# h2oiq_rev2.net
KiCad netlist of a schematic drawn in EAGLE
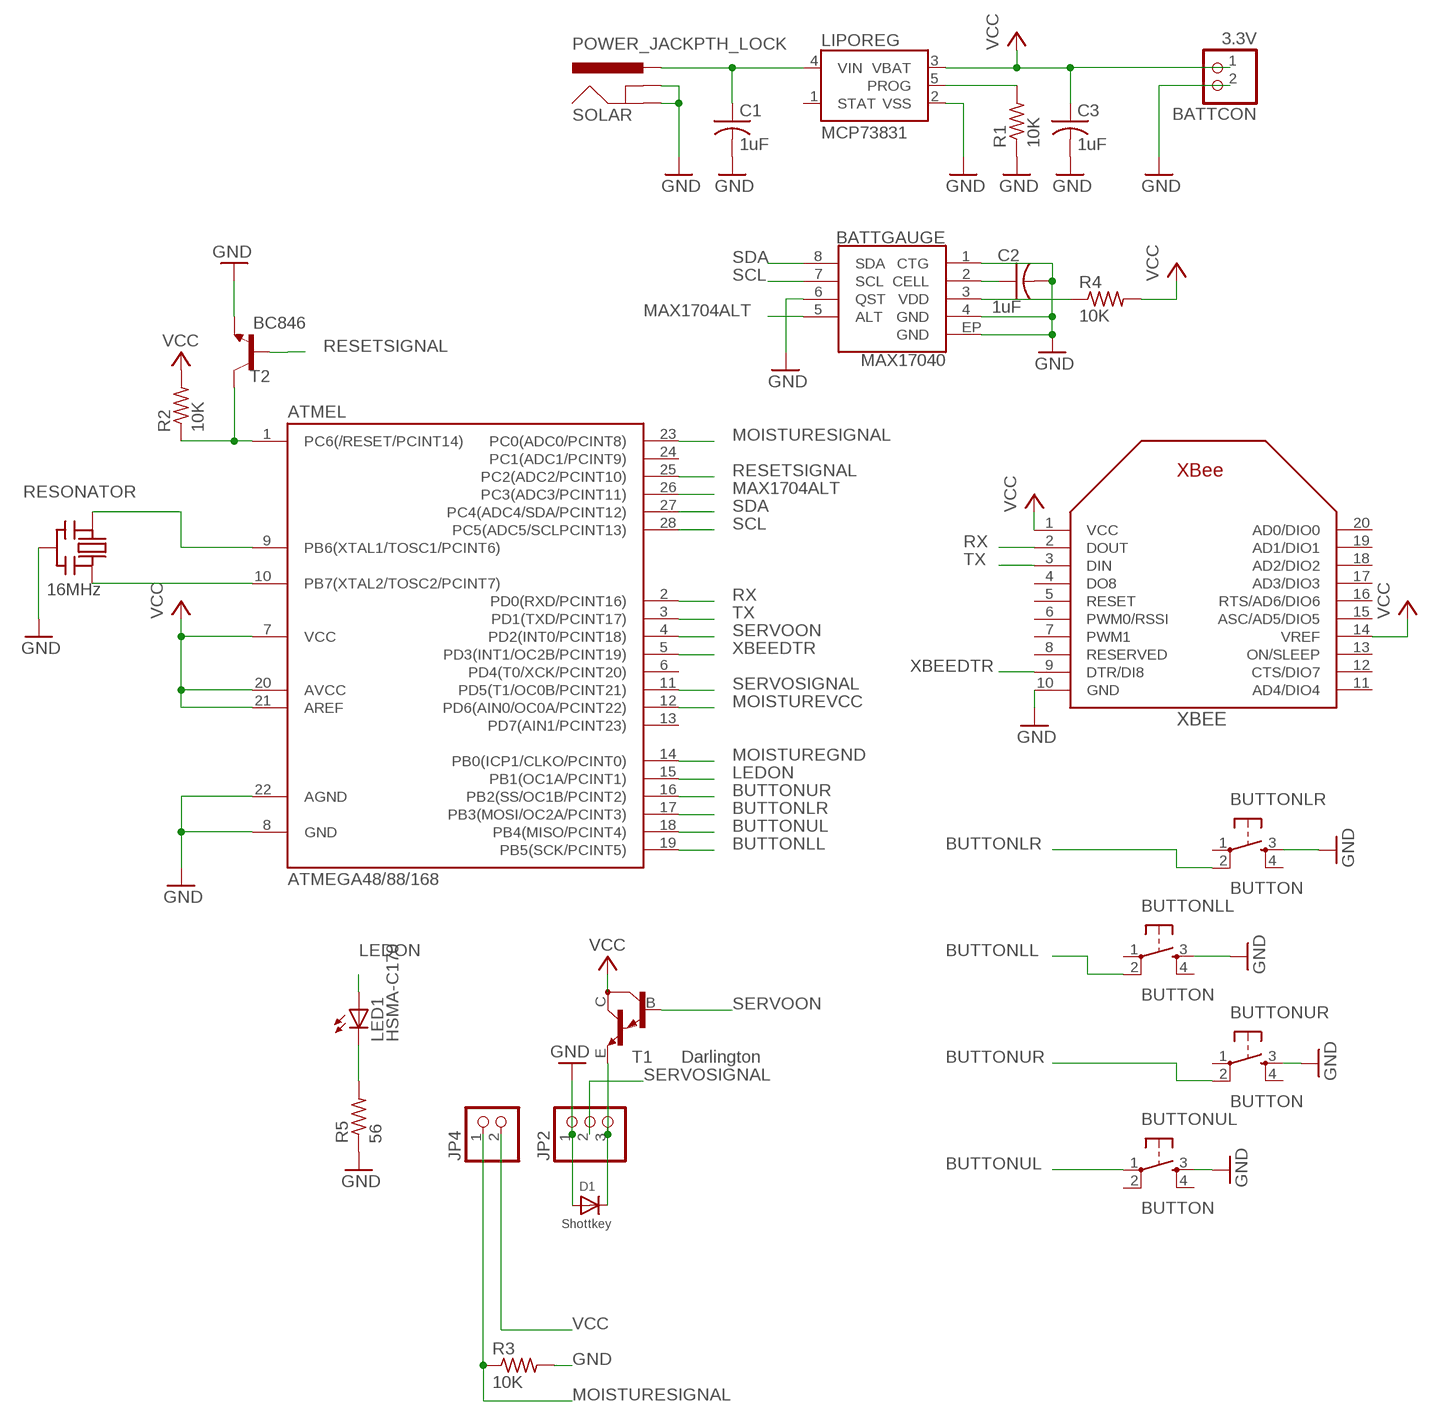
[diagram p0: schematic, sheet 1]

(export (version "E")
  (design (tool "Eeschema 10.0.6"))
  (components
    (comp (ref "ATMEL")
      (value "ATMEGA48/88/168")
      (footprint "eagle-import:DIL28-3")
      (libsource (lib "eagle-import") (part "MEGA48/88/168-PU"))
    )
    (comp (ref "BATTCON")
      (value "3.3V")
      (footprint "eagle-import:JST-PH-2-THM")
      (libsource (lib "eagle-import") (part "JST_2PIN-THM"))
    )
    (comp (ref "BATTGAUGE")
      (value "MAX17040")
      (footprint "eagle-import:MAX17040-TFDN")
      (libsource (lib "eagle-import") (part "MAX17040"))
    )
    (comp (ref "BUTTONLL")
      (value "BUTTON")
      (footprint "eagle-import:TACTILE-PTH")
      (libsource (lib "eagle-import") (part "TAC_SWITCHPTH"))
    )
    (comp (ref "BUTTONLR")
      (value "BUTTON")
      (footprint "eagle-import:TACTILE-PTH")
      (libsource (lib "eagle-import") (part "TAC_SWITCHPTH"))
    )
    (comp (ref "BUTTONUL")
      (value "BUTTON")
      (footprint "eagle-import:TACTILE-PTH")
      (libsource (lib "eagle-import") (part "TAC_SWITCHPTH"))
    )
    (comp (ref "BUTTONUR")
      (value "BUTTON")
      (footprint "eagle-import:TACTILE-PTH")
      (libsource (lib "eagle-import") (part "TAC_SWITCHPTH"))
    )
    (comp (ref "C1")
      (value "1uF")
      (footprint "eagle-import:C0603K")
      (libsource (lib "eagle-import") (part "C-USC0603K"))
    )
    (comp (ref "C2")
      (value "1uF")
      (footprint "eagle-import:C0603K")
      (libsource (lib "eagle-import") (part "C-USC0603K"))
    )
    (comp (ref "C3")
      (value "1uF")
      (footprint "eagle-import:C0603K")
      (libsource (lib "eagle-import") (part "C-USC0603K"))
    )
    (comp (ref "D1")
      (value "Shottkey")
      (footprint "eagle-import:SMADIODE")
      (libsource (lib "eagle-import") (part "DIODESMA"))
    )
    (comp (ref "JP2")
      (value "PINHD-1X3")
      (footprint "eagle-import:1X03")
      (libsource (lib "eagle-import") (part "PINHD-1X3"))
    )
    (comp (ref "JP4")
      (value "PINHD-1X2")
      (footprint "eagle-import:1X02")
      (libsource (lib "eagle-import") (part "PINHD-1X2"))
    )
    (comp (ref "LED1")
      (value "HSMA-C170")
      (footprint "eagle-import:LED-HSMA-SMD")
      (libsource (lib "eagle-import") (part "LED-HSMA-C170"))
    )
    (comp (ref "LIPOREG")
      (value "MCP73831")
      (footprint "eagle-import:SOT23-5")
      (libsource (lib "eagle-import") (part "MCP73831"))
    )
    (comp (ref "R1")
      (value "10K")
      (footprint "eagle-import:R0805")
      (libsource (lib "eagle-import") (part "R-US_R0805"))
    )
    (comp (ref "R2")
      (value "10K")
      (footprint "eagle-import:R0805")
      (libsource (lib "eagle-import") (part "R-US_R0805"))
    )
    (comp (ref "R3")
      (value "10K")
      (footprint "eagle-import:R0805")
      (libsource (lib "eagle-import") (part "R-US_R0805"))
    )
    (comp (ref "R4")
      (value "10K")
      (footprint "eagle-import:R0805")
      (libsource (lib "eagle-import") (part "R-US_R0805"))
    )
    (comp (ref "R5")
      (value "56")
      (footprint "eagle-import:R0805")
      (libsource (lib "eagle-import") (part "R-US_R0805"))
    )
    (comp (ref "RESONATOR")
      (value "16MHz")
      (footprint "eagle-import:CERM_OSC")
      (libsource (lib "eagle-import") (part "CERMOSCILL-THM"))
    )
    (comp (ref "SOLAR")
      (value "POWER_JACKPTH_LOCK")
      (footprint "eagle-import:POWER_JACK_PTH_LOCK")
      (libsource (lib "eagle-import") (part "POWER_JACKPTH_LOCK"))
    )
    (comp (ref "T1")
      (value "Darlington")
      (footprint "eagle-import:SOT23-BEC")
      (libsource (lib "eagle-import") (part "-NPN_DARL-SOT23-BECMMBTA13LT1"))
    )
    (comp (ref "T2")
      (value "BC846")
      (footprint "eagle-import:SOT23")
      (libsource (lib "eagle-import") (part "BC846"))
    )
    (comp (ref "XBEE")
      (value "XBEE")
      (footprint "eagle-import:XBEE")
      (libsource (lib "eagle-import") (part "XBEE"))
    )
  )
  (nets
    (net (code "1") (name "/BUTTONLL") (class "Default")
      (node (ref "ATMEL") (pin "19") (pinfunction "PB5(SCK/PCINT5)_19") (pintype "bidirectional"))
      (node (ref "BUTTONLL") (pin "2") (pinfunction "2_2") (pintype "passive"))
    )
    (net (code "2") (name "/BUTTONLR") (class "Default")
      (node (ref "ATMEL") (pin "17") (pinfunction "PB3(MOSI/OC2A/PCINT3)_17") (pintype "bidirectional"))
      (node (ref "BUTTONLR") (pin "2") (pinfunction "2_2") (pintype "passive"))
    )
    (net (code "3") (name "/BUTTONUL") (class "Default")
      (node (ref "ATMEL") (pin "18") (pinfunction "PB4(MISO/PCINT4)_18") (pintype "bidirectional"))
      (node (ref "BUTTONUL") (pin "1") (pinfunction "1_1") (pintype "passive"))
    )
    (net (code "4") (name "/BUTTONUR") (class "Default")
      (node (ref "ATMEL") (pin "16") (pinfunction "PB2(SS/OC1B/PCINT2)_16") (pintype "bidirectional"))
      (node (ref "BUTTONUR") (pin "2") (pinfunction "2_2") (pintype "passive"))
    )
    (net (code "5") (name "/LEDON") (class "Default")
      (node (ref "ATMEL") (pin "15") (pinfunction "PB1(OC1A/PCINT1)_15") (pintype "bidirectional"))
      (node (ref "LED1") (pin "P$1") (pinfunction "A_P$1") (pintype "passive"))
    )
    (net (code "6") (name "/MAX1704ALT") (class "Default")
      (node (ref "ATMEL") (pin "26") (pinfunction "PC3(ADC3/PCINT11)_26") (pintype "bidirectional"))
      (node (ref "BATTGAUGE") (pin "5") (pinfunction "ALT_5") (pintype "bidirectional"))
    )
    (net (code "7") (name "/MOISTUREGND") (class "Default")
      (node (ref "ATMEL") (pin "14") (pinfunction "PB0(ICP1/CLKO/PCINT0)_14") (pintype "bidirectional"))
    )
    (net (code "8") (name "/MOISTURESIGNAL") (class "Default")
      (node (ref "ATMEL") (pin "23") (pinfunction "PC0(ADC0/PCINT8)_23") (pintype "bidirectional"))
      (node (ref "JP4") (pin "1") (pinfunction "1_1") (pintype "passive"))
      (node (ref "R3") (pin "1") (pinfunction "1_1") (pintype "passive"))
    )
    (net (code "9") (name "/MOISTUREVCC") (class "Default")
      (node (ref "ATMEL") (pin "12") (pinfunction "PD6(AIN0/OC0A/PCINT22)_12") (pintype "bidirectional"))
    )
    (net (code "10") (name "/RESETSIGNAL") (class "Default")
      (node (ref "ATMEL") (pin "25") (pinfunction "PC2(ADC2/PCINT10)_25") (pintype "bidirectional"))
      (node (ref "T2") (pin "1") (pinfunction "B_1") (pintype "passive"))
    )
    (net (code "11") (name "/RX") (class "Default")
      (node (ref "ATMEL") (pin "2") (pinfunction "PD0(RXD/PCINT16)_2") (pintype "bidirectional"))
      (node (ref "XBEE") (pin "2") (pinfunction "DOUT_2") (pintype "output"))
    )
    (net (code "12") (name "/SCL") (class "Default")
      (node (ref "ATMEL") (pin "28") (pinfunction "PC5(ADC5/SCLPCINT13)_28") (pintype "bidirectional"))
      (node (ref "BATTGAUGE") (pin "7") (pinfunction "SCL_7") (pintype "bidirectional"))
    )
    (net (code "13") (name "/SDA") (class "Default")
      (node (ref "ATMEL") (pin "27") (pinfunction "PC4(ADC4/SDA/PCINT12)_27") (pintype "bidirectional"))
      (node (ref "BATTGAUGE") (pin "8") (pinfunction "SDA_8") (pintype "bidirectional"))
    )
    (net (code "14") (name "/SERVOON") (class "Default")
      (node (ref "ATMEL") (pin "4") (pinfunction "PD2(INT0/PCINT18)_4") (pintype "bidirectional"))
      (node (ref "T1") (pin "B") (pinfunction "B_B") (pintype "passive"))
    )
    (net (code "15") (name "/SERVOSIGNAL") (class "Default")
      (node (ref "ATMEL") (pin "11") (pinfunction "PD5(T1/OC0B/PCINT21)_11") (pintype "bidirectional"))
      (node (ref "JP2") (pin "2") (pinfunction "2_2") (pintype "passive"))
    )
    (net (code "16") (name "/TX") (class "Default")
      (node (ref "ATMEL") (pin "3") (pinfunction "PD1(TXD/PCINT17)_3") (pintype "bidirectional"))
      (node (ref "XBEE") (pin "3") (pinfunction "DIN_3") (pintype "input"))
    )
    (net (code "17") (name "/XBEEDTR") (class "Default")
      (node (ref "ATMEL") (pin "5") (pinfunction "PD3(INT1/OC2B/PCINT19)_5") (pintype "bidirectional"))
      (node (ref "XBEE") (pin "9") (pinfunction "DTR/DI8_9") (pintype "input"))
    )
    (net (code "18") (name "GND") (class "Default")
      (node (ref "ATMEL") (pin "22") (pinfunction "AGND_22") (pintype "power_in"))
      (node (ref "ATMEL") (pin "8") (pinfunction "GND_8") (pintype "power_in"))
      (node (ref "BATTCON") (pin "2") (pinfunction "1_2") (pintype "passive"))
      (node (ref "BATTGAUGE") (pin "1") (pinfunction "CTG_1") (pintype "bidirectional"))
      (node (ref "BATTGAUGE") (pin "4") (pinfunction "GND_4") (pintype "bidirectional"))
      (node (ref "BATTGAUGE") (pin "6") (pinfunction "QST_6") (pintype "bidirectional"))
      (node (ref "BATTGAUGE") (pin "EP") (pinfunction "GND_EP") (pintype "bidirectional"))
      (node (ref "BUTTONLL") (pin "3") (pinfunction "3_3") (pintype "passive"))
      (node (ref "BUTTONLR") (pin "3") (pinfunction "3_3") (pintype "passive"))
      (node (ref "BUTTONUL") (pin "3") (pinfunction "3_3") (pintype "passive"))
      (node (ref "BUTTONUR") (pin "3") (pinfunction "3_3") (pintype "passive"))
      (node (ref "C1") (pin "2") (pinfunction "2_2") (pintype "passive"))
      (node (ref "C2") (pin "2") (pinfunction "2_2") (pintype "passive"))
      (node (ref "C3") (pin "2") (pinfunction "2_2") (pintype "passive"))
      (node (ref "D1") (pin "A") (pinfunction "A_A") (pintype "passive"))
      (node (ref "JP2") (pin "1") (pinfunction "1_1") (pintype "passive"))
      (node (ref "LIPOREG") (pin "2") (pinfunction "VSS_2") (pintype "power_in"))
      (node (ref "R1") (pin "1") (pinfunction "1_1") (pintype "passive"))
      (node (ref "R3") (pin "2") (pinfunction "2_2") (pintype "passive"))
      (node (ref "R5") (pin "1") (pinfunction "1_1") (pintype "passive"))
      (node (ref "RESONATOR") (pin "P$2") (pinfunction "GND_P$2") (pintype "bidirectional"))
      (node (ref "SOLAR") (pin "GND") (pinfunction "GND_GND") (pintype "bidirectional"))
      (node (ref "SOLAR") (pin "GNDBREAK") (pinfunction "GNDBREAK_GNDBREAK") (pintype "bidirectional"))
      (node (ref "T2") (pin "2") (pinfunction "E_2") (pintype "passive"))
      (node (ref "XBEE") (pin "10") (pinfunction "GND_10") (pintype "power_in"))
    )
    (net (code "19") (name "Net-(ATMEL-PB6(XTAL1{slash}TOSC1{slash}PCINT6))") (class "Default")
      (node (ref "ATMEL") (pin "9") (pinfunction "PB6(XTAL1/TOSC1/PCINT6)_9") (pintype "bidirectional"))
      (node (ref "RESONATOR") (pin "P$1") (pinfunction "IN_P$1") (pintype "bidirectional"))
    )
    (net (code "20") (name "Net-(ATMEL-PB7(XTAL2{slash}TOSC2{slash}PCINT7))") (class "Default")
      (node (ref "ATMEL") (pin "10") (pinfunction "PB7(XTAL2/TOSC2/PCINT7)_10") (pintype "bidirectional"))
      (node (ref "RESONATOR") (pin "P$3") (pinfunction "OUT_P$3") (pintype "bidirectional"))
    )
    (net (code "21") (name "Net-(ATMEL-PC6({slash}RESET{slash}PCINT14))") (class "Default")
      (node (ref "ATMEL") (pin "1") (pinfunction "PC6(/RESET/PCINT14)_1") (pintype "bidirectional"))
      (node (ref "R2") (pin "1") (pinfunction "1_1") (pintype "passive"))
      (node (ref "T2") (pin "3") (pinfunction "C_3") (pintype "passive"))
    )
    (net (code "22") (name "Net-(BATTGAUGE-CELL)") (class "Default")
      (node (ref "BATTGAUGE") (pin "2") (pinfunction "CELL_2") (pintype "bidirectional"))
      (node (ref "C2") (pin "1") (pinfunction "1_1") (pintype "passive"))
    )
    (net (code "23") (name "Net-(BATTGAUGE-VDD)") (class "Default")
      (node (ref "BATTGAUGE") (pin "3") (pinfunction "VDD_3") (pintype "bidirectional"))
      (node (ref "R4") (pin "1") (pinfunction "1_1") (pintype "passive"))
    )
    (net (code "24") (name "Net-(D1-PadC)") (class "Default")
      (node (ref "D1") (pin "C") (pinfunction "C_C") (pintype "passive"))
      (node (ref "JP2") (pin "3") (pinfunction "3_3") (pintype "passive"))
      (node (ref "T1") (pin "E") (pinfunction "E_E") (pintype "passive"))
    )
    (net (code "25") (name "Net-(LED1-C)") (class "Default")
      (node (ref "LED1") (pin "P$2") (pinfunction "C_P$2") (pintype "passive"))
      (node (ref "R5") (pin "2") (pinfunction "2_2") (pintype "passive"))
    )
    (net (code "26") (name "Net-(LIPOREG-PROG)") (class "Default")
      (node (ref "LIPOREG") (pin "5") (pinfunction "PROG_5") (pintype "input"))
      (node (ref "R1") (pin "2") (pinfunction "2_2") (pintype "passive"))
    )
    (net (code "27") (name "Net-(LIPOREG-VIN)") (class "Default")
      (node (ref "C1") (pin "1") (pinfunction "1_1") (pintype "passive"))
      (node (ref "LIPOREG") (pin "4") (pinfunction "VIN_4") (pintype "power_in"))
      (node (ref "SOLAR") (pin "PWR") (pinfunction "PWR_PWR") (pintype "bidirectional"))
    )
    (net (code "28") (name "VCC") (class "Default")
      (node (ref "ATMEL") (pin "20") (pinfunction "AVCC_20") (pintype "passive"))
      (node (ref "ATMEL") (pin "21") (pinfunction "AREF_21") (pintype "passive"))
      (node (ref "ATMEL") (pin "7") (pinfunction "VCC_7") (pintype "power_in"))
      (node (ref "BATTCON") (pin "1") (pinfunction "2_1") (pintype "passive"))
      (node (ref "C3") (pin "1") (pinfunction "1_1") (pintype "passive"))
      (node (ref "JP4") (pin "2") (pinfunction "2_2") (pintype "passive"))
      (node (ref "LIPOREG") (pin "3") (pinfunction "VBAT_3") (pintype "power_in"))
      (node (ref "R2") (pin "2") (pinfunction "2_2") (pintype "passive"))
      (node (ref "R4") (pin "2") (pinfunction "2_2") (pintype "passive"))
      (node (ref "T1") (pin "C") (pinfunction "C_C") (pintype "passive"))
      (node (ref "XBEE") (pin "1") (pinfunction "VCC_1") (pintype "power_in"))
      (node (ref "XBEE") (pin "14") (pinfunction "VREF_14") (pintype "input"))
    )
    (net (code "29") (name "unconnected-(ATMEL-PC1(ADC1{slash}PCINT9)-Pad24)") (class "Default")
      (node (ref "ATMEL") (pin "24") (pinfunction "PC1(ADC1/PCINT9)_24") (pintype "bidirectional"))
    )
    (net (code "30") (name "unconnected-(ATMEL-PD4(T0{slash}XCK{slash}PCINT20)-Pad6)") (class "Default")
      (node (ref "ATMEL") (pin "6") (pinfunction "PD4(T0/XCK/PCINT20)_6") (pintype "bidirectional"))
    )
    (net (code "31") (name "unconnected-(ATMEL-PD7(AIN1{slash}PCINT23)-Pad13)") (class "Default")
      (node (ref "ATMEL") (pin "13") (pinfunction "PD7(AIN1/PCINT23)_13") (pintype "bidirectional"))
    )
    (net (code "32") (name "unconnected-(BUTTONLL-Pad1)") (class "Default")
      (node (ref "BUTTONLL") (pin "1") (pinfunction "1_1") (pintype "passive"))
    )
    (net (code "33") (name "unconnected-(BUTTONLL-Pad4)") (class "Default")
      (node (ref "BUTTONLL") (pin "4") (pinfunction "4_4") (pintype "passive"))
    )
    (net (code "34") (name "unconnected-(BUTTONLR-Pad1)") (class "Default")
      (node (ref "BUTTONLR") (pin "1") (pinfunction "1_1") (pintype "passive"))
    )
    (net (code "35") (name "unconnected-(BUTTONLR-Pad4)") (class "Default")
      (node (ref "BUTTONLR") (pin "4") (pinfunction "4_4") (pintype "passive"))
    )
    (net (code "36") (name "unconnected-(BUTTONUL-Pad2)") (class "Default")
      (node (ref "BUTTONUL") (pin "2") (pinfunction "2_2") (pintype "passive"))
    )
    (net (code "37") (name "unconnected-(BUTTONUL-Pad4)") (class "Default")
      (node (ref "BUTTONUL") (pin "4") (pinfunction "4_4") (pintype "passive"))
    )
    (net (code "38") (name "unconnected-(BUTTONUR-Pad1)") (class "Default")
      (node (ref "BUTTONUR") (pin "1") (pinfunction "1_1") (pintype "passive"))
    )
    (net (code "39") (name "unconnected-(BUTTONUR-Pad4)") (class "Default")
      (node (ref "BUTTONUR") (pin "4") (pinfunction "4_4") (pintype "passive"))
    )
    (net (code "40") (name "unconnected-(LIPOREG-STAT-Pad1)") (class "Default")
      (node (ref "LIPOREG") (pin "1") (pinfunction "STAT_1") (pintype "output"))
    )
    (net (code "41") (name "unconnected-(XBEE-AD0{slash}DIO0-Pad20)") (class "Default")
      (node (ref "XBEE") (pin "20") (pinfunction "AD0/DIO0_20") (pintype "bidirectional"))
    )
    (net (code "42") (name "unconnected-(XBEE-AD1{slash}DIO1-Pad19)") (class "Default")
      (node (ref "XBEE") (pin "19") (pinfunction "AD1/DIO1_19") (pintype "bidirectional"))
    )
    (net (code "43") (name "unconnected-(XBEE-AD2{slash}DIO2-Pad18)") (class "Default")
      (node (ref "XBEE") (pin "18") (pinfunction "AD2/DIO2_18") (pintype "bidirectional"))
    )
    (net (code "44") (name "unconnected-(XBEE-AD3{slash}DIO3-Pad17)") (class "Default")
      (node (ref "XBEE") (pin "17") (pinfunction "AD3/DIO3_17") (pintype "bidirectional"))
    )
    (net (code "45") (name "unconnected-(XBEE-AD4{slash}DIO4-Pad11)") (class "Default")
      (node (ref "XBEE") (pin "11") (pinfunction "AD4/DIO4_11") (pintype "bidirectional"))
    )
    (net (code "46") (name "unconnected-(XBEE-ASC{slash}AD5{slash}DIO5-Pad15)") (class "Default")
      (node (ref "XBEE") (pin "15") (pinfunction "ASC/AD5/DIO5_15") (pintype "bidirectional"))
    )
    (net (code "47") (name "unconnected-(XBEE-CTS{slash}DIO7-Pad12)") (class "Default")
      (node (ref "XBEE") (pin "12") (pinfunction "CTS/DIO7_12") (pintype "bidirectional"))
    )
    (net (code "48") (name "unconnected-(XBEE-DO8-Pad4)") (class "Default")
      (node (ref "XBEE") (pin "4") (pinfunction "DO8_4") (pintype "output"))
    )
    (net (code "49") (name "unconnected-(XBEE-ON{slash}SLEEP-Pad13)") (class "Default")
      (node (ref "XBEE") (pin "13") (pinfunction "ON/SLEEP_13") (pintype "output"))
    )
    (net (code "50") (name "unconnected-(XBEE-PWM0{slash}RSSI-Pad6)") (class "Default")
      (node (ref "XBEE") (pin "6") (pinfunction "PWM0/RSSI_6") (pintype "output"))
    )
    (net (code "51") (name "unconnected-(XBEE-PWM1-Pad7)") (class "Default")
      (node (ref "XBEE") (pin "7") (pinfunction "PWM1_7") (pintype "output"))
    )
    (net (code "52") (name "unconnected-(XBEE-RESERVED-Pad8)") (class "Default")
      (node (ref "XBEE") (pin "8") (pinfunction "RESERVED_8") (pintype "no_connect"))
    )
    (net (code "53") (name "unconnected-(XBEE-RESET-Pad5)") (class "Default")
      (node (ref "XBEE") (pin "5") (pinfunction "RESET_5") (pintype "input"))
    )
    (net (code "54") (name "unconnected-(XBEE-RTS{slash}AD6{slash}DIO6-Pad16)") (class "Default")
      (node (ref "XBEE") (pin "16") (pinfunction "RTS/AD6/DIO6_16") (pintype "bidirectional"))
    )
  )
)
